# AC_Switch_Proto.net
KiCad netlist of a schematic drawn in EAGLE
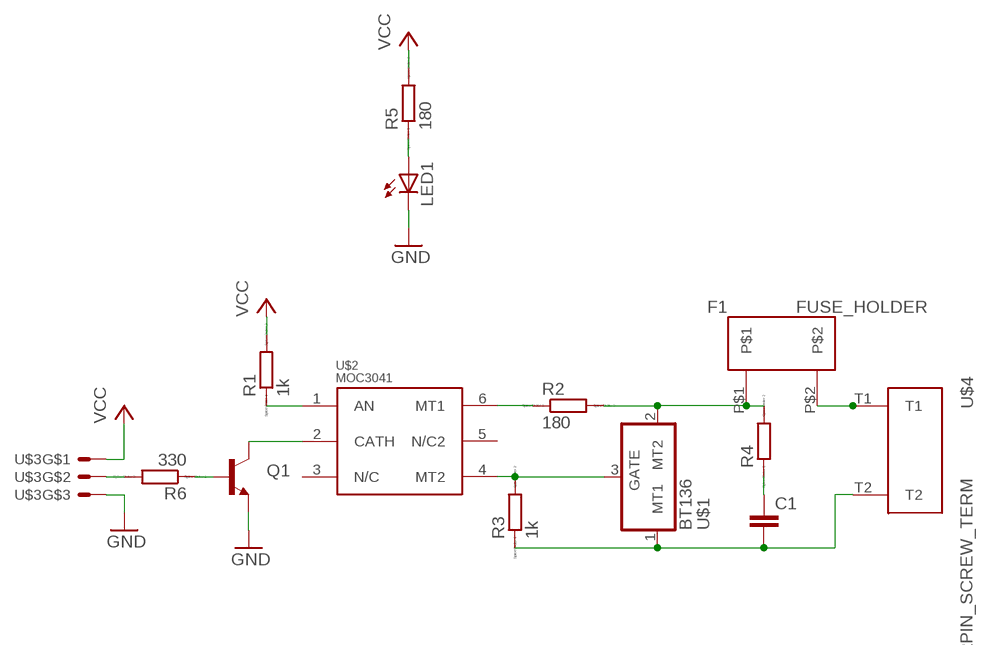
[diagram p0: schematic, sheet 1]

(export (version "E")
  (design (tool "Eeschema 10.0.6"))
  (components
    (comp (ref "C1")
      (value "C-EU050-030X075")
      (footprint "eagle-import:C050-030X075")
      (libsource (lib "eagle-import") (part "C-EU050-030X075"))
    )
    (comp (ref "F1")
      (value "FUSE_HOLDER")
      (footprint "eagle-import:FUSE_HOLDER")
      (libsource (lib "eagle-import") (part "FUSE_HOLDER"))
    )
    (comp (ref "LED1")
      (value "LED3MM")
      (footprint "eagle-import:LED3MM")
      (libsource (lib "eagle-import") (part "LED3MM"))
    )
    (comp (ref "Q1")
      (value "TRANSISTOR_NPNBC547")
      (footprint "eagle-import:TO-92-AMMO")
      (libsource (lib "eagle-import") (part "TRANSISTOR_NPNBC547"))
    )
    (comp (ref "R1")
      (value "1k")
      (footprint "eagle-import:0207_10")
      (libsource (lib "eagle-import") (part "R0207/10"))
    )
    (comp (ref "R2")
      (value "180")
      (footprint "eagle-import:0207_10")
      (libsource (lib "eagle-import") (part "R0207/10"))
    )
    (comp (ref "R3")
      (value "1k")
      (footprint "eagle-import:0207_10")
      (libsource (lib "eagle-import") (part "R0207/10"))
    )
    (comp (ref "R4")
      (value "R0207/10")
      (footprint "eagle-import:0207_10")
      (libsource (lib "eagle-import") (part "R0207/10"))
    )
    (comp (ref "R5")
      (value "180")
      (footprint "eagle-import:0207_10")
      (libsource (lib "eagle-import") (part "R0207/10"))
    )
    (comp (ref "R6")
      (value "330")
      (footprint "eagle-import:0207_10")
      (libsource (lib "eagle-import") (part "R0207/10"))
    )
    (comp (ref "U$1")
      (value "BT136")
      (footprint "eagle-import:BT136")
      (libsource (lib "eagle-import") (part "BT136"))
    )
    (comp (ref "U$2")
      (value "MOC3041")
      (footprint "eagle-import:MOC3041")
      (libsource (lib "eagle-import") (part "MOC3041"))
    )
    (comp (ref "U$3")
      (value "3PINHEADER")
      (footprint "eagle-import:3PINHEADER")
      (libsource (lib "eagle-import") (part "3PINHEADER"))
    )
    (comp (ref "U$4")
      (value "2PIN_SCREW_TERM")
      (footprint "eagle-import:2PIN_SCREW_TERM")
      (libsource (lib "eagle-import") (part "2PIN_SCREW_TERM"))
    )
  )
  (nets
    (net (code "1") (name "GND") (class "Default")
      (node (ref "LED1") (pin "K") (pinfunction "C_K") (pintype "passive"))
      (node (ref "Q1") (pin "3") (pinfunction "E_3") (pintype "passive"))
      (node (ref "U$3") (pin "N2") (pinfunction "S_N2") (pintype "passive"))
    )
    (net (code "2") (name "Net-(C1-Pad1)") (class "Default")
      (node (ref "C1") (pin "1") (pinfunction "1_1") (pintype "passive"))
      (node (ref "R4") (pin "1") (pinfunction "1_1") (pintype "passive"))
    )
    (net (code "3") (name "Net-(F1-PadP$2)") (class "Default")
      (node (ref "F1") (pin "P$2") (pinfunction "P$2_P$2") (pintype "bidirectional"))
      (node (ref "U$4") (pin "T1") (pinfunction "T1_T1") (pintype "bidirectional"))
    )
    (net (code "4") (name "Net-(LED1-PadA)") (class "Default")
      (node (ref "LED1") (pin "A") (pinfunction "A_A") (pintype "passive"))
      (node (ref "R5") (pin "1") (pinfunction "1_1") (pintype "passive"))
    )
    (net (code "5") (name "Net-(Q1-B)") (class "Default")
      (node (ref "Q1") (pin "2") (pinfunction "B_2") (pintype "passive"))
      (node (ref "R6") (pin "1") (pinfunction "1_1") (pintype "passive"))
    )
    (net (code "6") (name "Net-(Q1-C)") (class "Default")
      (node (ref "Q1") (pin "1") (pinfunction "C_1") (pintype "passive"))
      (node (ref "U$2") (pin "2") (pinfunction "CATH_2") (pintype "bidirectional"))
    )
    (net (code "7") (name "Net-(U$1-GATE)") (class "Default")
      (node (ref "R3") (pin "2") (pinfunction "2_2") (pintype "passive"))
      (node (ref "U$1") (pin "3") (pinfunction "GATE_3") (pintype "input"))
      (node (ref "U$2") (pin "4") (pinfunction "MT2_4") (pintype "bidirectional"))
    )
    (net (code "8") (name "Net-(U$1-MT1)") (class "Default")
      (node (ref "C1") (pin "2") (pinfunction "2_2") (pintype "passive"))
      (node (ref "R3") (pin "1") (pinfunction "1_1") (pintype "passive"))
      (node (ref "U$1") (pin "1") (pinfunction "MT1_1") (pintype "input"))
      (node (ref "U$4") (pin "T2") (pinfunction "T2_T2") (pintype "bidirectional"))
    )
    (net (code "9") (name "Net-(U$1-MT2)") (class "Default")
      (node (ref "F1") (pin "P$1") (pinfunction "P$1_P$1") (pintype "bidirectional"))
      (node (ref "R2") (pin "2") (pinfunction "2_2") (pintype "passive"))
      (node (ref "R4") (pin "2") (pinfunction "2_2") (pintype "passive"))
      (node (ref "U$1") (pin "2") (pinfunction "MT2_2") (pintype "passive"))
    )
    (net (code "10") (name "Net-(U$2-AN)") (class "Default")
      (node (ref "R1") (pin "1") (pinfunction "1_1") (pintype "passive"))
      (node (ref "U$2") (pin "1") (pinfunction "AN_1") (pintype "bidirectional"))
    )
    (net (code "11") (name "Net-(U$2-MT1)") (class "Default")
      (node (ref "R2") (pin "1") (pinfunction "1_1") (pintype "passive"))
      (node (ref "U$2") (pin "6") (pinfunction "MT1_6") (pintype "bidirectional"))
    )
    (net (code "12") (name "Net-(U$3B-S)") (class "Default")
      (node (ref "R6") (pin "2") (pinfunction "2_2") (pintype "passive"))
      (node (ref "U$3") (pin "N1") (pinfunction "S_N1") (pintype "passive"))
    )
    (net (code "13") (name "VCC") (class "Default")
      (node (ref "R1") (pin "2") (pinfunction "2_2") (pintype "passive"))
      (node (ref "R5") (pin "2") (pinfunction "2_2") (pintype "passive"))
      (node (ref "U$3") (pin "N0") (pinfunction "S_N0") (pintype "passive"))
    )
    (net (code "14") (name "unconnected-(U$2-N{slash}C-Pad3)") (class "Default")
      (node (ref "U$2") (pin "3") (pinfunction "N/C_3") (pintype "bidirectional"))
    )
    (net (code "15") (name "unconnected-(U$2-N{slash}C2-Pad5)") (class "Default")
      (node (ref "U$2") (pin "5") (pinfunction "N/C2_5") (pintype "bidirectional"))
    )
  )
)
